# pic16f877_general_shematic.net
KiCad netlist of a schematic drawn in EAGLE
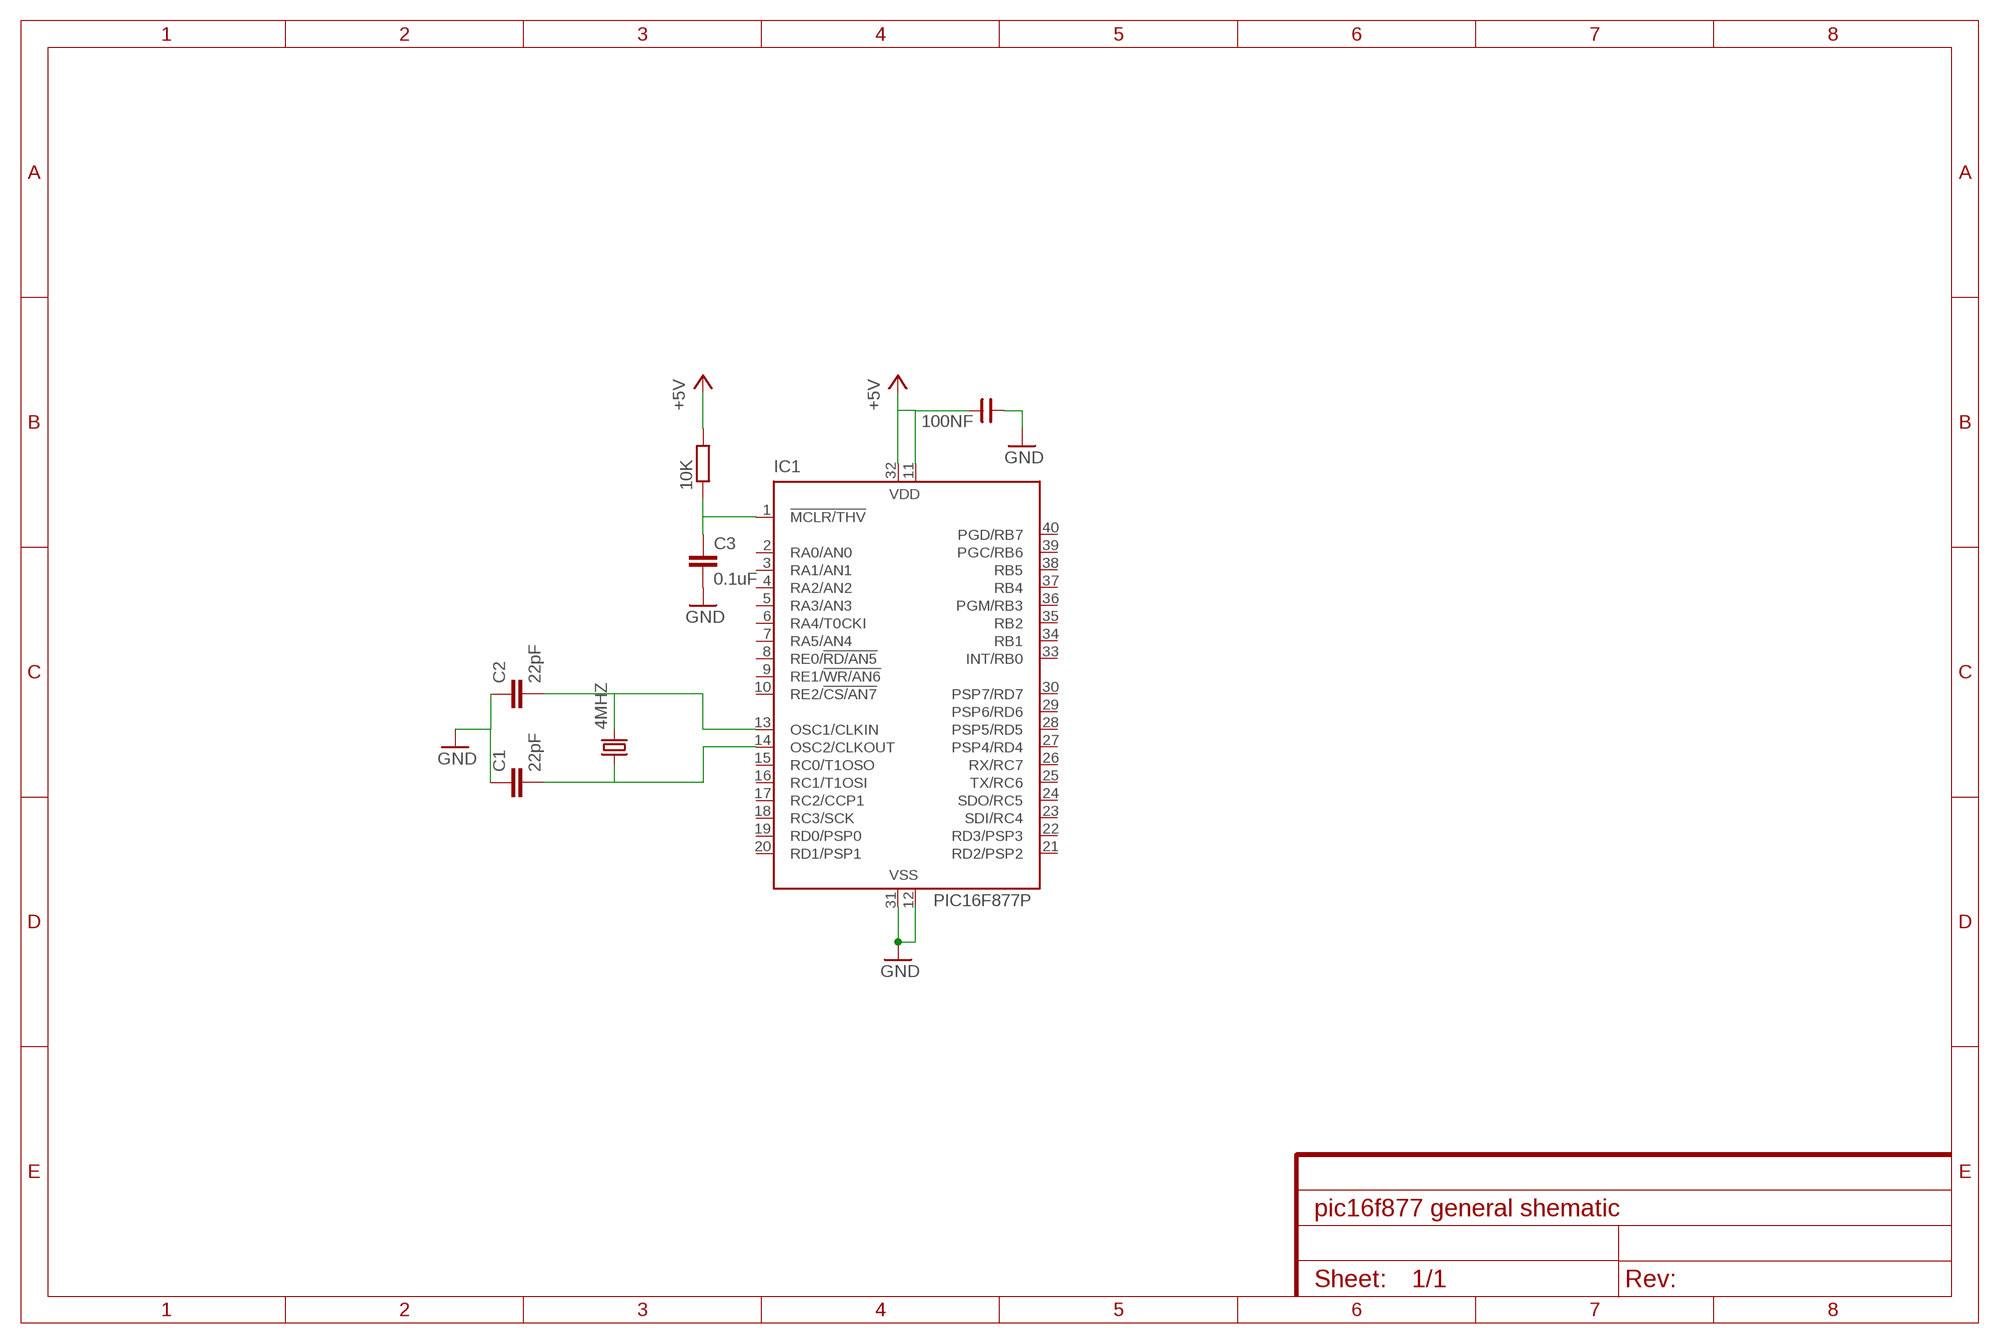
[diagram p0: schematic, sheet 1]

(export (version "E")
  (design (tool "Eeschema 10.0.6"))
  (components
    (comp (ref "4MHZ")
      (value "CRYSTALHC49U-V")
      (footprint "eagle-import:HC49U-V")
      (libsource (lib "eagle-import") (part "CRYSTALHC49U-V"))
    )
    (comp (ref "10K")
      (value "R0204/7")
      (footprint "eagle-import:0204_7")
      (libsource (lib "eagle-import") (part "R0204/7"))
    )
    (comp (ref "100NF")
      (value "CNP-0402")
      (footprint "eagle-import:0402")
      (libsource (lib "eagle-import") (part "CNP-0402"))
    )
    (comp (ref "C1")
      (value "22pF")
      (footprint "eagle-import:0603")
      (libsource (lib "eagle-import") (part "22PF-0603-50V-5%"))
    )
    (comp (ref "C2")
      (value "22pF")
      (footprint "eagle-import:0603")
      (libsource (lib "eagle-import") (part "22PF-0603-50V-5%"))
    )
    (comp (ref "C3")
      (value "0.1uF")
      (footprint "eagle-import:0402-CAP")
      (libsource (lib "eagle-import") (part ".1UF-CER"))
    )
    (comp (ref "IC1")
      (value "PIC16F877P")
      (footprint "eagle-import:DIL40")
      (fields (field (name "MF") "MICROCHIP") (field (name "MPN") "PIC16F877-04/P"))
      (libsource (lib "eagle-import") (part "PIC16F87P7"))
    )
  )
  (nets
    (net (code "1") (name "+5V") (class "Default")
      (node (ref "100NF") (pin "2") (pinfunction "2_2") (pintype "passive"))
      (node (ref "10K") (pin "2") (pinfunction "2_2") (pintype "passive"))
      (node (ref "IC1") (pin "11") (pinfunction "VDD_11") (pintype "power_in"))
      (node (ref "IC1") (pin "32") (pinfunction "VDD_32") (pintype "power_in"))
    )
    (net (code "2") (name "GND") (class "Default")
      (node (ref "100NF") (pin "1") (pinfunction "1_1") (pintype "passive"))
      (node (ref "C1") (pin "1") (pinfunction "1_1") (pintype "passive"))
      (node (ref "C2") (pin "1") (pinfunction "1_1") (pintype "passive"))
      (node (ref "C3") (pin "2") (pinfunction "2_2") (pintype "passive"))
      (node (ref "IC1") (pin "12") (pinfunction "VSS_12") (pintype "power_in"))
      (node (ref "IC1") (pin "31") (pinfunction "VSS_31") (pintype "power_in"))
    )
    (net (code "3") (name "Net-(IC1-OSC1{slash}CLKIN)") (class "Default")
      (node (ref "4MHZ") (pin "2") (pinfunction "2_2") (pintype "passive"))
      (node (ref "C2") (pin "2") (pinfunction "2_2") (pintype "passive"))
      (node (ref "IC1") (pin "13") (pinfunction "OSC1/CLKIN_13") (pintype "input"))
    )
    (net (code "4") (name "Net-(IC1-OSC2{slash}CLKOUT)") (class "Default")
      (node (ref "4MHZ") (pin "1") (pinfunction "1_1") (pintype "passive"))
      (node (ref "C1") (pin "2") (pinfunction "2_2") (pintype "passive"))
      (node (ref "IC1") (pin "14") (pinfunction "OSC2/CLKOUT_14") (pintype "output"))
    )
    (net (code "5") (name "Net-(IC1-~{MCLR{slash}THV})") (class "Default")
      (node (ref "10K") (pin "1") (pinfunction "1_1") (pintype "passive"))
      (node (ref "C3") (pin "1") (pinfunction "1_1") (pintype "passive"))
      (node (ref "IC1") (pin "1") (pinfunction "~{MCLR/THV}_1") (pintype "input"))
    )
    (net (code "6") (name "unconnected-(IC1-INT{slash}RB0-Pad33)") (class "Default")
      (node (ref "IC1") (pin "33") (pinfunction "INT/RB0_33") (pintype "bidirectional"))
    )
    (net (code "7") (name "unconnected-(IC1-PGC{slash}RB6-Pad39)") (class "Default")
      (node (ref "IC1") (pin "39") (pinfunction "PGC/RB6_39") (pintype "bidirectional"))
    )
    (net (code "8") (name "unconnected-(IC1-PGD{slash}RB7-Pad40)") (class "Default")
      (node (ref "IC1") (pin "40") (pinfunction "PGD/RB7_40") (pintype "bidirectional"))
    )
    (net (code "9") (name "unconnected-(IC1-PGM{slash}RB3-Pad36)") (class "Default")
      (node (ref "IC1") (pin "36") (pinfunction "PGM/RB3_36") (pintype "bidirectional"))
    )
    (net (code "10") (name "unconnected-(IC1-PSP4{slash}RD4-Pad27)") (class "Default")
      (node (ref "IC1") (pin "27") (pinfunction "PSP4/RD4_27") (pintype "bidirectional"))
    )
    (net (code "11") (name "unconnected-(IC1-PSP5{slash}RD5-Pad28)") (class "Default")
      (node (ref "IC1") (pin "28") (pinfunction "PSP5/RD5_28") (pintype "bidirectional"))
    )
    (net (code "12") (name "unconnected-(IC1-PSP6{slash}RD6-Pad29)") (class "Default")
      (node (ref "IC1") (pin "29") (pinfunction "PSP6/RD6_29") (pintype "bidirectional"))
    )
    (net (code "13") (name "unconnected-(IC1-PSP7{slash}RD7-Pad30)") (class "Default")
      (node (ref "IC1") (pin "30") (pinfunction "PSP7/RD7_30") (pintype "bidirectional"))
    )
    (net (code "14") (name "unconnected-(IC1-RA0{slash}AN0-Pad2)") (class "Default")
      (node (ref "IC1") (pin "2") (pinfunction "RA0/AN0_2") (pintype "bidirectional"))
    )
    (net (code "15") (name "unconnected-(IC1-RA1{slash}AN1-Pad3)") (class "Default")
      (node (ref "IC1") (pin "3") (pinfunction "RA1/AN1_3") (pintype "bidirectional"))
    )
    (net (code "16") (name "unconnected-(IC1-RA2{slash}AN2-Pad4)") (class "Default")
      (node (ref "IC1") (pin "4") (pinfunction "RA2/AN2_4") (pintype "bidirectional"))
    )
    (net (code "17") (name "unconnected-(IC1-RA3{slash}AN3-Pad5)") (class "Default")
      (node (ref "IC1") (pin "5") (pinfunction "RA3/AN3_5") (pintype "bidirectional"))
    )
    (net (code "18") (name "unconnected-(IC1-RA4{slash}T0CKI-Pad6)") (class "Default")
      (node (ref "IC1") (pin "6") (pinfunction "RA4/T0CKI_6") (pintype "bidirectional"))
    )
    (net (code "19") (name "unconnected-(IC1-RA5{slash}AN4-Pad7)") (class "Default")
      (node (ref "IC1") (pin "7") (pinfunction "RA5/AN4_7") (pintype "bidirectional"))
    )
    (net (code "20") (name "unconnected-(IC1-RB1-Pad34)") (class "Default")
      (node (ref "IC1") (pin "34") (pinfunction "RB1_34") (pintype "bidirectional"))
    )
    (net (code "21") (name "unconnected-(IC1-RB2-Pad35)") (class "Default")
      (node (ref "IC1") (pin "35") (pinfunction "RB2_35") (pintype "bidirectional"))
    )
    (net (code "22") (name "unconnected-(IC1-RB4-Pad37)") (class "Default")
      (node (ref "IC1") (pin "37") (pinfunction "RB4_37") (pintype "bidirectional"))
    )
    (net (code "23") (name "unconnected-(IC1-RB5-Pad38)") (class "Default")
      (node (ref "IC1") (pin "38") (pinfunction "RB5_38") (pintype "bidirectional"))
    )
    (net (code "24") (name "unconnected-(IC1-RC0{slash}T1OSO-Pad15)") (class "Default")
      (node (ref "IC1") (pin "15") (pinfunction "RC0/T1OSO_15") (pintype "bidirectional"))
    )
    (net (code "25") (name "unconnected-(IC1-RC1{slash}T1OSI-Pad16)") (class "Default")
      (node (ref "IC1") (pin "16") (pinfunction "RC1/T1OSI_16") (pintype "bidirectional"))
    )
    (net (code "26") (name "unconnected-(IC1-RC2{slash}CCP1-Pad17)") (class "Default")
      (node (ref "IC1") (pin "17") (pinfunction "RC2/CCP1_17") (pintype "bidirectional"))
    )
    (net (code "27") (name "unconnected-(IC1-RC3{slash}SCK-Pad18)") (class "Default")
      (node (ref "IC1") (pin "18") (pinfunction "RC3/SCK_18") (pintype "bidirectional"))
    )
    (net (code "28") (name "unconnected-(IC1-RD0{slash}PSP0-Pad19)") (class "Default")
      (node (ref "IC1") (pin "19") (pinfunction "RD0/PSP0_19") (pintype "bidirectional"))
    )
    (net (code "29") (name "unconnected-(IC1-RD1{slash}PSP1-Pad20)") (class "Default")
      (node (ref "IC1") (pin "20") (pinfunction "RD1/PSP1_20") (pintype "bidirectional"))
    )
    (net (code "30") (name "unconnected-(IC1-RD2{slash}PSP2-Pad21)") (class "Default")
      (node (ref "IC1") (pin "21") (pinfunction "RD2/PSP2_21") (pintype "bidirectional"))
    )
    (net (code "31") (name "unconnected-(IC1-RD3{slash}PSP3-Pad22)") (class "Default")
      (node (ref "IC1") (pin "22") (pinfunction "RD3/PSP3_22") (pintype "bidirectional"))
    )
    (net (code "32") (name "unconnected-(IC1-RE0{slash}~{RD{slash}AN5}-Pad8)") (class "Default")
      (node (ref "IC1") (pin "8") (pinfunction "RE0/~{RD/AN5}_8") (pintype "bidirectional"))
    )
    (net (code "33") (name "unconnected-(IC1-RE1{slash}~{WR{slash}AN6}-Pad9)") (class "Default")
      (node (ref "IC1") (pin "9") (pinfunction "RE1/~{WR/AN6}_9") (pintype "bidirectional"))
    )
    (net (code "34") (name "unconnected-(IC1-RE2{slash}~{CS{slash}AN7}-Pad10)") (class "Default")
      (node (ref "IC1") (pin "10") (pinfunction "RE2/~{CS/AN7}_10") (pintype "bidirectional"))
    )
    (net (code "35") (name "unconnected-(IC1-RX{slash}RC7-Pad26)") (class "Default")
      (node (ref "IC1") (pin "26") (pinfunction "RX/RC7_26") (pintype "bidirectional"))
    )
    (net (code "36") (name "unconnected-(IC1-SDI{slash}RC4-Pad23)") (class "Default")
      (node (ref "IC1") (pin "23") (pinfunction "SDI/RC4_23") (pintype "bidirectional"))
    )
    (net (code "37") (name "unconnected-(IC1-SDO{slash}RC5-Pad24)") (class "Default")
      (node (ref "IC1") (pin "24") (pinfunction "SDO/RC5_24") (pintype "bidirectional"))
    )
    (net (code "38") (name "unconnected-(IC1-TX{slash}RC6-Pad25)") (class "Default")
      (node (ref "IC1") (pin "25") (pinfunction "TX/RC6_25") (pintype "bidirectional"))
    )
  )
)
